# board_2.net
KiCad netlist of a schematic drawn in EAGLE
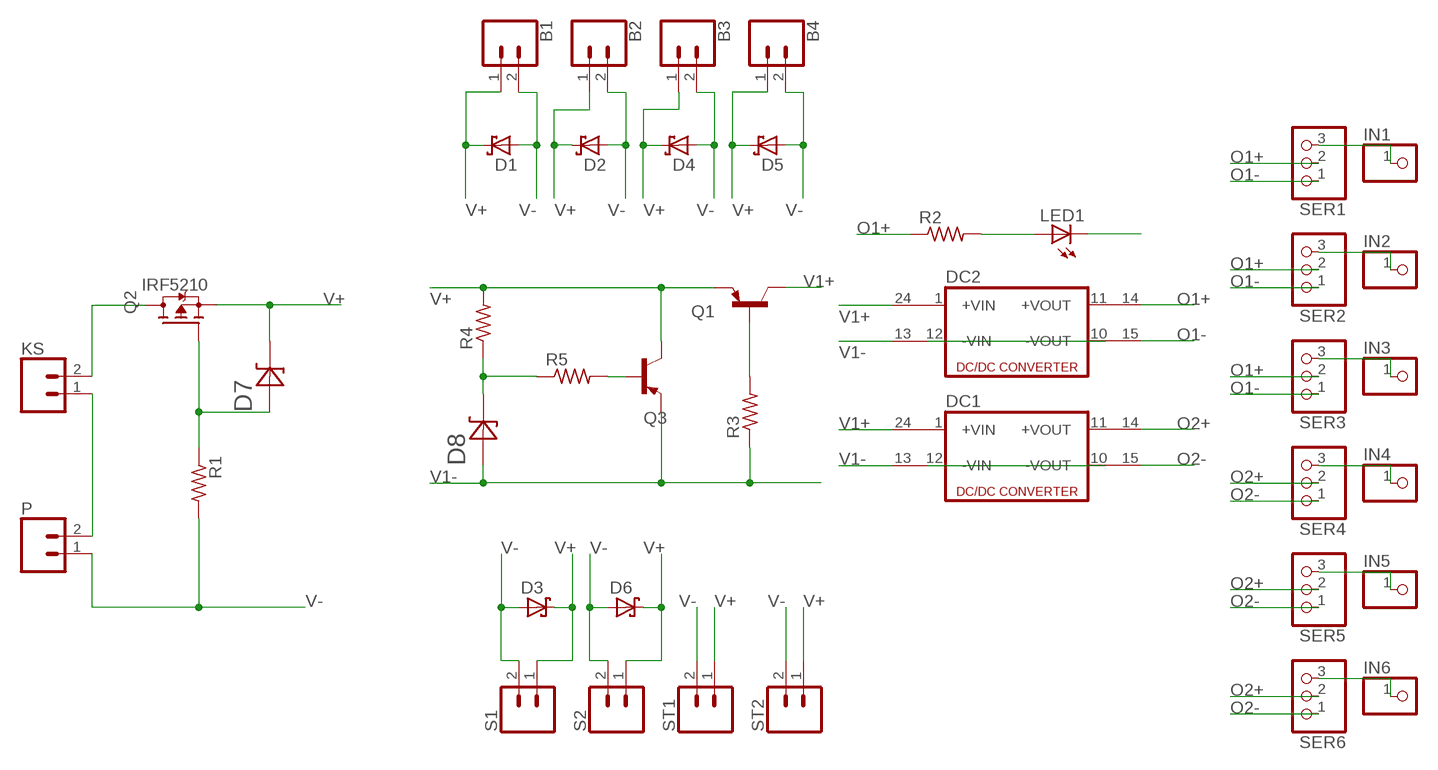
[diagram p0: schematic, sheet 1]

(export (version "E")
  (design (tool "Eeschema 10.0.6"))
  (components
    (comp (ref "B1")
      (value "CONN_02")
      (footprint "eagle-import:1X02")
      (libsource (lib "eagle-import") (part "CONN_02"))
    )
    (comp (ref "B2")
      (value "CONN_02")
      (footprint "eagle-import:1X02")
      (libsource (lib "eagle-import") (part "CONN_02"))
    )
    (comp (ref "B3")
      (value "CONN_02")
      (footprint "eagle-import:1X02")
      (libsource (lib "eagle-import") (part "CONN_02"))
    )
    (comp (ref "B4")
      (value "CONN_02")
      (footprint "eagle-import:1X02")
      (libsource (lib "eagle-import") (part "CONN_02"))
    )
    (comp (ref "D1")
      (value "SCHOTTKY-DIODEF126Z12")
      (footprint "eagle-import:F126Z12")
      (libsource (lib "eagle-import") (part "SCHOTTKY-DIODEF126Z12"))
    )
    (comp (ref "D2")
      (value "SCHOTTKY-DIODEF126Z12")
      (footprint "eagle-import:F126Z12")
      (libsource (lib "eagle-import") (part "SCHOTTKY-DIODEF126Z12"))
    )
    (comp (ref "D3")
      (value "SCHOTTKY-DIODEF126Z12")
      (footprint "eagle-import:F126Z12")
      (libsource (lib "eagle-import") (part "SCHOTTKY-DIODEF126Z12"))
    )
    (comp (ref "D4")
      (value "SCHOTTKY-DIODEF126Z12")
      (footprint "eagle-import:F126Z12")
      (libsource (lib "eagle-import") (part "SCHOTTKY-DIODEF126Z12"))
    )
    (comp (ref "D5")
      (value "SCHOTTKY-DIODEF126Z12")
      (footprint "eagle-import:F126Z12")
      (libsource (lib "eagle-import") (part "SCHOTTKY-DIODEF126Z12"))
    )
    (comp (ref "D6")
      (value "SCHOTTKY-DIODEF126Z12")
      (footprint "eagle-import:F126Z12")
      (libsource (lib "eagle-import") (part "SCHOTTKY-DIODEF126Z12"))
    )
    (comp (ref "D7")
      (value "1N4752A-T")
      (footprint "eagle-import:DIOAD1060W80L410D260")
      (fields (field (name "MF") "ON Semiconductor") (field (name "MP") "1N4752A"))
      (libsource (lib "eagle-import") (part "1N4752A-T"))
    )
    (comp (ref "D8")
      (value "1N4752A-T")
      (footprint "eagle-import:DIOAD1060W80L410D260")
      (fields (field (name "MF") "ON Semiconductor") (field (name "MP") "1N4752A"))
      (libsource (lib "eagle-import") (part "1N4752A-T"))
    )
    (comp (ref "DC1")
      (value "DC213R")
      (footprint "eagle-import:CMK")
      (libsource (lib "eagle-import") (part "DC213R"))
    )
    (comp (ref "DC2")
      (value "DC213R")
      (footprint "eagle-import:CMK")
      (libsource (lib "eagle-import") (part "DC213R"))
    )
    (comp (ref "IN1")
      (value "PINHD-1X1")
      (footprint "eagle-import:1X01")
      (libsource (lib "eagle-import") (part "PINHD-1X1"))
    )
    (comp (ref "IN2")
      (value "PINHD-1X1")
      (footprint "eagle-import:1X01")
      (libsource (lib "eagle-import") (part "PINHD-1X1"))
    )
    (comp (ref "IN3")
      (value "PINHD-1X1")
      (footprint "eagle-import:1X01")
      (libsource (lib "eagle-import") (part "PINHD-1X1"))
    )
    (comp (ref "IN4")
      (value "PINHD-1X1")
      (footprint "eagle-import:1X01")
      (libsource (lib "eagle-import") (part "PINHD-1X1"))
    )
    (comp (ref "IN5")
      (value "PINHD-1X1")
      (footprint "eagle-import:1X01")
      (libsource (lib "eagle-import") (part "PINHD-1X1"))
    )
    (comp (ref "IN6")
      (value "PINHD-1X1")
      (footprint "eagle-import:1X01")
      (libsource (lib "eagle-import") (part "PINHD-1X1"))
    )
    (comp (ref "KS")
      (value "CONN_02")
      (footprint "eagle-import:1X02")
      (libsource (lib "eagle-import") (part "CONN_02"))
    )
    (comp (ref "LED1")
      (value "LED5MM")
      (footprint "eagle-import:LED5MM")
      (libsource (lib "eagle-import") (part "LED5MM"))
    )
    (comp (ref "P")
      (value "CONN_02")
      (footprint "eagle-import:1X02")
      (libsource (lib "eagle-import") (part "CONN_02"))
    )
    (comp (ref "Q1")
      (value "2N2907")
      (footprint "eagle-import:TO92-EBC-OVAL")
      (libsource (lib "eagle-import") (part "2N2907"))
    )
    (comp (ref "Q2")
      (value "IRF5210")
      (footprint "eagle-import:TO254P1054X469X2933-3")
      (fields (field (name "MF") "Infineon Technologies"))
      (libsource (lib "eagle-import") (part "IRF5210"))
    )
    (comp (ref "Q3")
      (value "2N2907")
      (footprint "eagle-import:TO92-EBC-OVAL")
      (libsource (lib "eagle-import") (part "2N2907"))
    )
    (comp (ref "R1")
      (value "R-US_0204/7")
      (footprint "eagle-import:0204_7")
      (libsource (lib "eagle-import") (part "R-US_0204/7"))
    )
    (comp (ref "R2")
      (value "R-US_0204/7")
      (footprint "eagle-import:0204_7")
      (libsource (lib "eagle-import") (part "R-US_0204/7"))
    )
    (comp (ref "R3")
      (value "R-US_0204/7")
      (footprint "eagle-import:0204_7")
      (libsource (lib "eagle-import") (part "R-US_0204/7"))
    )
    (comp (ref "R4")
      (value "R-US_0204/7")
      (footprint "eagle-import:0204_7")
      (libsource (lib "eagle-import") (part "R-US_0204/7"))
    )
    (comp (ref "R5")
      (value "R-US_0204/7")
      (footprint "eagle-import:0204_7")
      (libsource (lib "eagle-import") (part "R-US_0204/7"))
    )
    (comp (ref "S1")
      (value "CONN_02")
      (footprint "eagle-import:1X02")
      (libsource (lib "eagle-import") (part "CONN_02"))
    )
    (comp (ref "S2")
      (value "CONN_02")
      (footprint "eagle-import:1X02")
      (libsource (lib "eagle-import") (part "CONN_02"))
    )
    (comp (ref "SER1")
      (value "PINHD-1X3")
      (footprint "eagle-import:1X03")
      (libsource (lib "eagle-import") (part "PINHD-1X3"))
    )
    (comp (ref "SER2")
      (value "PINHD-1X3")
      (footprint "eagle-import:1X03")
      (libsource (lib "eagle-import") (part "PINHD-1X3"))
    )
    (comp (ref "SER3")
      (value "PINHD-1X3")
      (footprint "eagle-import:1X03")
      (libsource (lib "eagle-import") (part "PINHD-1X3"))
    )
    (comp (ref "SER4")
      (value "PINHD-1X3")
      (footprint "eagle-import:1X03")
      (libsource (lib "eagle-import") (part "PINHD-1X3"))
    )
    (comp (ref "SER5")
      (value "PINHD-1X3")
      (footprint "eagle-import:1X03")
      (libsource (lib "eagle-import") (part "PINHD-1X3"))
    )
    (comp (ref "SER6")
      (value "PINHD-1X3")
      (footprint "eagle-import:1X03")
      (libsource (lib "eagle-import") (part "PINHD-1X3"))
    )
    (comp (ref "ST1")
      (value "CONN_02")
      (footprint "eagle-import:1X02")
      (libsource (lib "eagle-import") (part "CONN_02"))
    )
    (comp (ref "ST2")
      (value "CONN_02")
      (footprint "eagle-import:1X02")
      (libsource (lib "eagle-import") (part "CONN_02"))
    )
  )
  (nets
    (net (code "1") (name "/O1+") (class "Default")
      (node (ref "DC2") (pin "14") (pinfunction "+VOUT1_14") (pintype "passive"))
      (node (ref "R2") (pin "1") (pinfunction "1_1") (pintype "passive"))
      (node (ref "SER1") (pin "2") (pinfunction "2_2") (pintype "passive"))
      (node (ref "SER2") (pin "2") (pinfunction "2_2") (pintype "passive"))
      (node (ref "SER3") (pin "2") (pinfunction "2_2") (pintype "passive"))
    )
    (net (code "2") (name "/O1-") (class "Default")
      (node (ref "DC2") (pin "15") (pinfunction "-VOUT1_15") (pintype "passive"))
      (node (ref "SER1") (pin "1") (pinfunction "1_1") (pintype "passive"))
      (node (ref "SER2") (pin "1") (pinfunction "1_1") (pintype "passive"))
      (node (ref "SER3") (pin "1") (pinfunction "1_1") (pintype "passive"))
    )
    (net (code "3") (name "/O2+") (class "Default")
      (node (ref "DC1") (pin "14") (pinfunction "+VOUT1_14") (pintype "passive"))
      (node (ref "SER4") (pin "2") (pinfunction "2_2") (pintype "passive"))
      (node (ref "SER5") (pin "2") (pinfunction "2_2") (pintype "passive"))
      (node (ref "SER6") (pin "2") (pinfunction "2_2") (pintype "passive"))
    )
    (net (code "4") (name "/O2-") (class "Default")
      (node (ref "DC1") (pin "15") (pinfunction "-VOUT1_15") (pintype "passive"))
      (node (ref "SER4") (pin "1") (pinfunction "1_1") (pintype "passive"))
      (node (ref "SER5") (pin "1") (pinfunction "1_1") (pintype "passive"))
      (node (ref "SER6") (pin "1") (pinfunction "1_1") (pintype "passive"))
    )
    (net (code "5") (name "/V+") (class "Default")
      (node (ref "B1") (pin "1") (pinfunction "1_1") (pintype "passive"))
      (node (ref "B2") (pin "1") (pinfunction "1_1") (pintype "passive"))
      (node (ref "B3") (pin "1") (pinfunction "1_1") (pintype "passive"))
      (node (ref "B4") (pin "1") (pinfunction "1_1") (pintype "passive"))
      (node (ref "D1") (pin "C") (pinfunction "C_C") (pintype "passive"))
      (node (ref "D2") (pin "C") (pinfunction "C_C") (pintype "passive"))
      (node (ref "D3") (pin "C") (pinfunction "C_C") (pintype "passive"))
      (node (ref "D4") (pin "C") (pinfunction "C_C") (pintype "passive"))
      (node (ref "D5") (pin "C") (pinfunction "C_C") (pintype "passive"))
      (node (ref "D6") (pin "C") (pinfunction "C_C") (pintype "passive"))
      (node (ref "D7") (pin "C") (pinfunction "C_C") (pintype "passive"))
      (node (ref "Q1") (pin "E") (pinfunction "E_E") (pintype "passive"))
      (node (ref "Q2") (pin "3") (pinfunction "S_3") (pintype "passive"))
      (node (ref "Q3") (pin "C") (pinfunction "C_C") (pintype "passive"))
      (node (ref "R4") (pin "2") (pinfunction "2_2") (pintype "passive"))
      (node (ref "S1") (pin "1") (pinfunction "1_1") (pintype "passive"))
      (node (ref "S2") (pin "1") (pinfunction "1_1") (pintype "passive"))
      (node (ref "ST1") (pin "1") (pinfunction "1_1") (pintype "passive"))
      (node (ref "ST2") (pin "1") (pinfunction "1_1") (pintype "passive"))
    )
    (net (code "6") (name "/V-") (class "Default")
      (node (ref "B1") (pin "2") (pinfunction "2_2") (pintype "passive"))
      (node (ref "B2") (pin "2") (pinfunction "2_2") (pintype "passive"))
      (node (ref "B3") (pin "2") (pinfunction "2_2") (pintype "passive"))
      (node (ref "B4") (pin "2") (pinfunction "2_2") (pintype "passive"))
      (node (ref "D1") (pin "A") (pinfunction "A_A") (pintype "passive"))
      (node (ref "D2") (pin "A") (pinfunction "A_A") (pintype "passive"))
      (node (ref "D3") (pin "A") (pinfunction "A_A") (pintype "passive"))
      (node (ref "D4") (pin "A") (pinfunction "A_A") (pintype "passive"))
      (node (ref "D5") (pin "A") (pinfunction "A_A") (pintype "passive"))
      (node (ref "D6") (pin "A") (pinfunction "A_A") (pintype "passive"))
      (node (ref "P") (pin "1") (pinfunction "1_1") (pintype "passive"))
      (node (ref "R1") (pin "2") (pinfunction "2_2") (pintype "passive"))
      (node (ref "S1") (pin "2") (pinfunction "2_2") (pintype "passive"))
      (node (ref "S2") (pin "2") (pinfunction "2_2") (pintype "passive"))
      (node (ref "ST1") (pin "2") (pinfunction "2_2") (pintype "passive"))
      (node (ref "ST2") (pin "2") (pinfunction "2_2") (pintype "passive"))
    )
    (net (code "7") (name "/V1+") (class "Default")
      (node (ref "DC1") (pin "24") (pinfunction "+VIN1_24") (pintype "passive"))
      (node (ref "DC2") (pin "24") (pinfunction "+VIN1_24") (pintype "passive"))
      (node (ref "Q1") (pin "C") (pinfunction "C_C") (pintype "passive"))
    )
    (net (code "8") (name "/V1-") (class "Default")
      (node (ref "D8") (pin "A") (pinfunction "A_A") (pintype "passive"))
      (node (ref "DC1") (pin "13") (pinfunction "-VIN1_13") (pintype "passive"))
      (node (ref "DC2") (pin "13") (pinfunction "-VIN1_13") (pintype "passive"))
      (node (ref "Q3") (pin "E") (pinfunction "E_E") (pintype "passive"))
      (node (ref "R3") (pin "1") (pinfunction "1_1") (pintype "passive"))
    )
    (net (code "9") (name "Net-(D8-PadC)") (class "Default")
      (node (ref "D8") (pin "C") (pinfunction "C_C") (pintype "passive"))
      (node (ref "R4") (pin "1") (pinfunction "1_1") (pintype "passive"))
      (node (ref "R5") (pin "1") (pinfunction "1_1") (pintype "passive"))
    )
    (net (code "10") (name "Net-(DC1--VIN)") (class "Default")
      (node (ref "DC1") (pin "10") (pinfunction "-VOUT_10") (pintype "passive"))
      (node (ref "DC1") (pin "12") (pinfunction "-VIN_12") (pintype "passive"))
    )
    (net (code "11") (name "Net-(DC2--VIN)") (class "Default")
      (node (ref "DC2") (pin "10") (pinfunction "-VOUT_10") (pintype "passive"))
      (node (ref "DC2") (pin "12") (pinfunction "-VIN_12") (pintype "passive"))
    )
    (net (code "12") (name "Net-(IN1-Pad1)") (class "Default")
      (node (ref "IN1") (pin "1") (pinfunction "1_1") (pintype "passive"))
      (node (ref "SER1") (pin "3") (pinfunction "3_3") (pintype "passive"))
    )
    (net (code "13") (name "Net-(IN2-Pad1)") (class "Default")
      (node (ref "IN2") (pin "1") (pinfunction "1_1") (pintype "passive"))
      (node (ref "SER2") (pin "3") (pinfunction "3_3") (pintype "passive"))
    )
    (net (code "14") (name "Net-(IN3-Pad1)") (class "Default")
      (node (ref "IN3") (pin "1") (pinfunction "1_1") (pintype "passive"))
      (node (ref "SER3") (pin "3") (pinfunction "3_3") (pintype "passive"))
    )
    (net (code "15") (name "Net-(IN4-Pad1)") (class "Default")
      (node (ref "IN4") (pin "1") (pinfunction "1_1") (pintype "passive"))
      (node (ref "SER4") (pin "3") (pinfunction "3_3") (pintype "passive"))
    )
    (net (code "16") (name "Net-(IN5-Pad1)") (class "Default")
      (node (ref "IN5") (pin "1") (pinfunction "1_1") (pintype "passive"))
      (node (ref "SER5") (pin "3") (pinfunction "3_3") (pintype "passive"))
    )
    (net (code "17") (name "Net-(IN6-Pad1)") (class "Default")
      (node (ref "IN6") (pin "1") (pinfunction "1_1") (pintype "passive"))
      (node (ref "SER6") (pin "3") (pinfunction "3_3") (pintype "passive"))
    )
    (net (code "18") (name "Net-(KS-Pad1)") (class "Default")
      (node (ref "KS") (pin "1") (pinfunction "1_1") (pintype "passive"))
      (node (ref "P") (pin "2") (pinfunction "2_2") (pintype "passive"))
    )
    (net (code "19") (name "Net-(LED1-PadA)") (class "Default")
      (node (ref "LED1") (pin "A") (pinfunction "A_A") (pintype "passive"))
      (node (ref "R2") (pin "2") (pinfunction "2_2") (pintype "passive"))
    )
    (net (code "20") (name "Net-(Q1-PadB)") (class "Default")
      (node (ref "Q1") (pin "B") (pinfunction "B_B") (pintype "passive"))
      (node (ref "R3") (pin "2") (pinfunction "2_2") (pintype "passive"))
    )
    (net (code "21") (name "Net-(Q2-D)") (class "Default")
      (node (ref "KS") (pin "2") (pinfunction "2_2") (pintype "passive"))
      (node (ref "Q2") (pin "2") (pinfunction "D_2") (pintype "passive"))
    )
    (net (code "22") (name "Net-(Q2-G)") (class "Default")
      (node (ref "D7") (pin "A") (pinfunction "A_A") (pintype "passive"))
      (node (ref "Q2") (pin "1") (pinfunction "G_1") (pintype "passive"))
      (node (ref "R1") (pin "1") (pinfunction "1_1") (pintype "passive"))
    )
    (net (code "23") (name "Net-(Q3-PadB)") (class "Default")
      (node (ref "Q3") (pin "B") (pinfunction "B_B") (pintype "passive"))
      (node (ref "R5") (pin "2") (pinfunction "2_2") (pintype "passive"))
    )
    (net (code "24") (name "unconnected-(DC1-+VIN-Pad1)") (class "Default")
      (node (ref "DC1") (pin "1") (pinfunction "+VIN_1") (pintype "passive"))
    )
    (net (code "25") (name "unconnected-(DC1-+VOUT-Pad11)") (class "Default")
      (node (ref "DC1") (pin "11") (pinfunction "+VOUT_11") (pintype "passive"))
    )
    (net (code "26") (name "unconnected-(DC2-+VIN-Pad1)") (class "Default")
      (node (ref "DC2") (pin "1") (pinfunction "+VIN_1") (pintype "passive"))
    )
    (net (code "27") (name "unconnected-(DC2-+VOUT-Pad11)") (class "Default")
      (node (ref "DC2") (pin "11") (pinfunction "+VOUT_11") (pintype "passive"))
    )
    (net (code "28") (name "unconnected-(LED1-C-PadK)") (class "Default")
      (node (ref "LED1") (pin "K") (pinfunction "C_K") (pintype "passive"))
    )
  )
)
